# 06_MIMXRT1170_PART2.net
KiCad netlist of a schematic drawn in Altium Designer
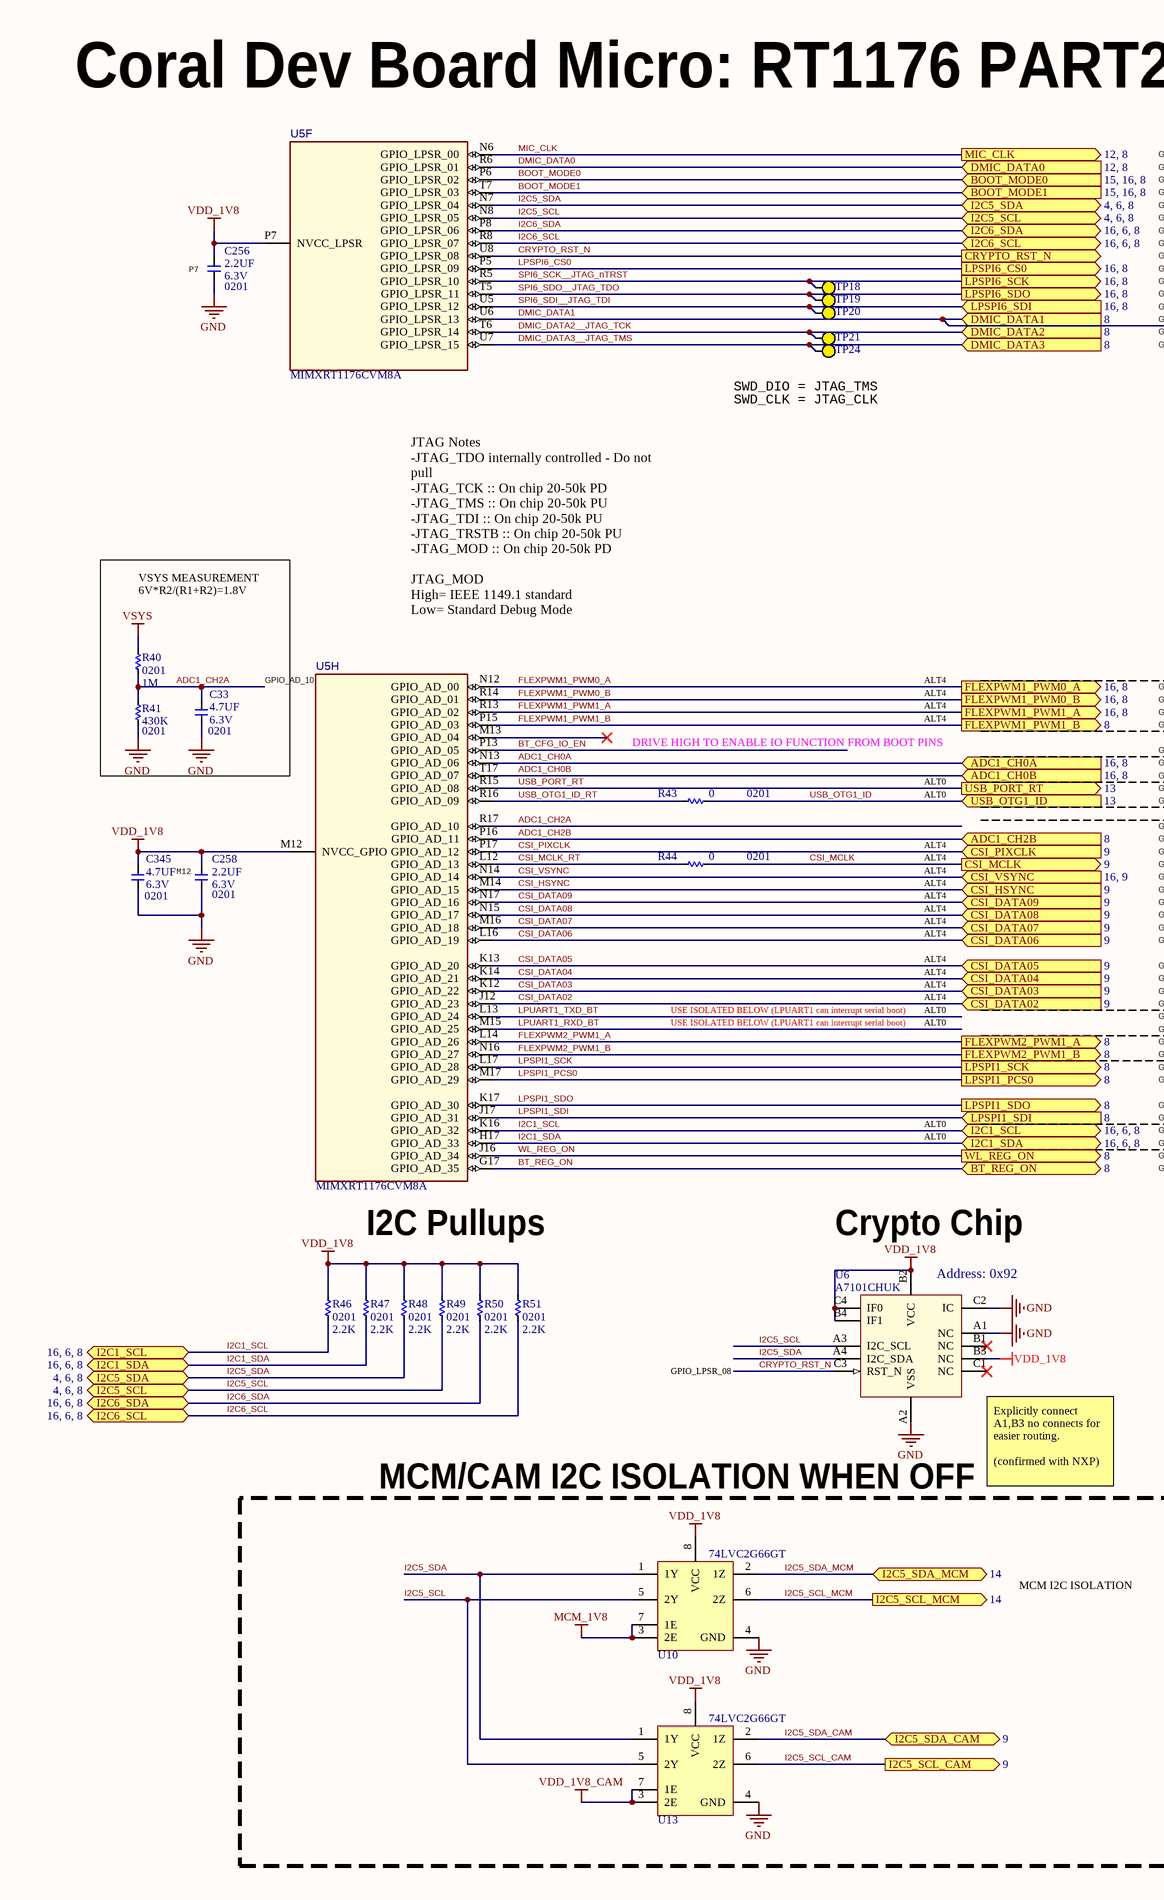
[diagram p0: 06 MIMXRT1170 PART2.SchDoc, left]
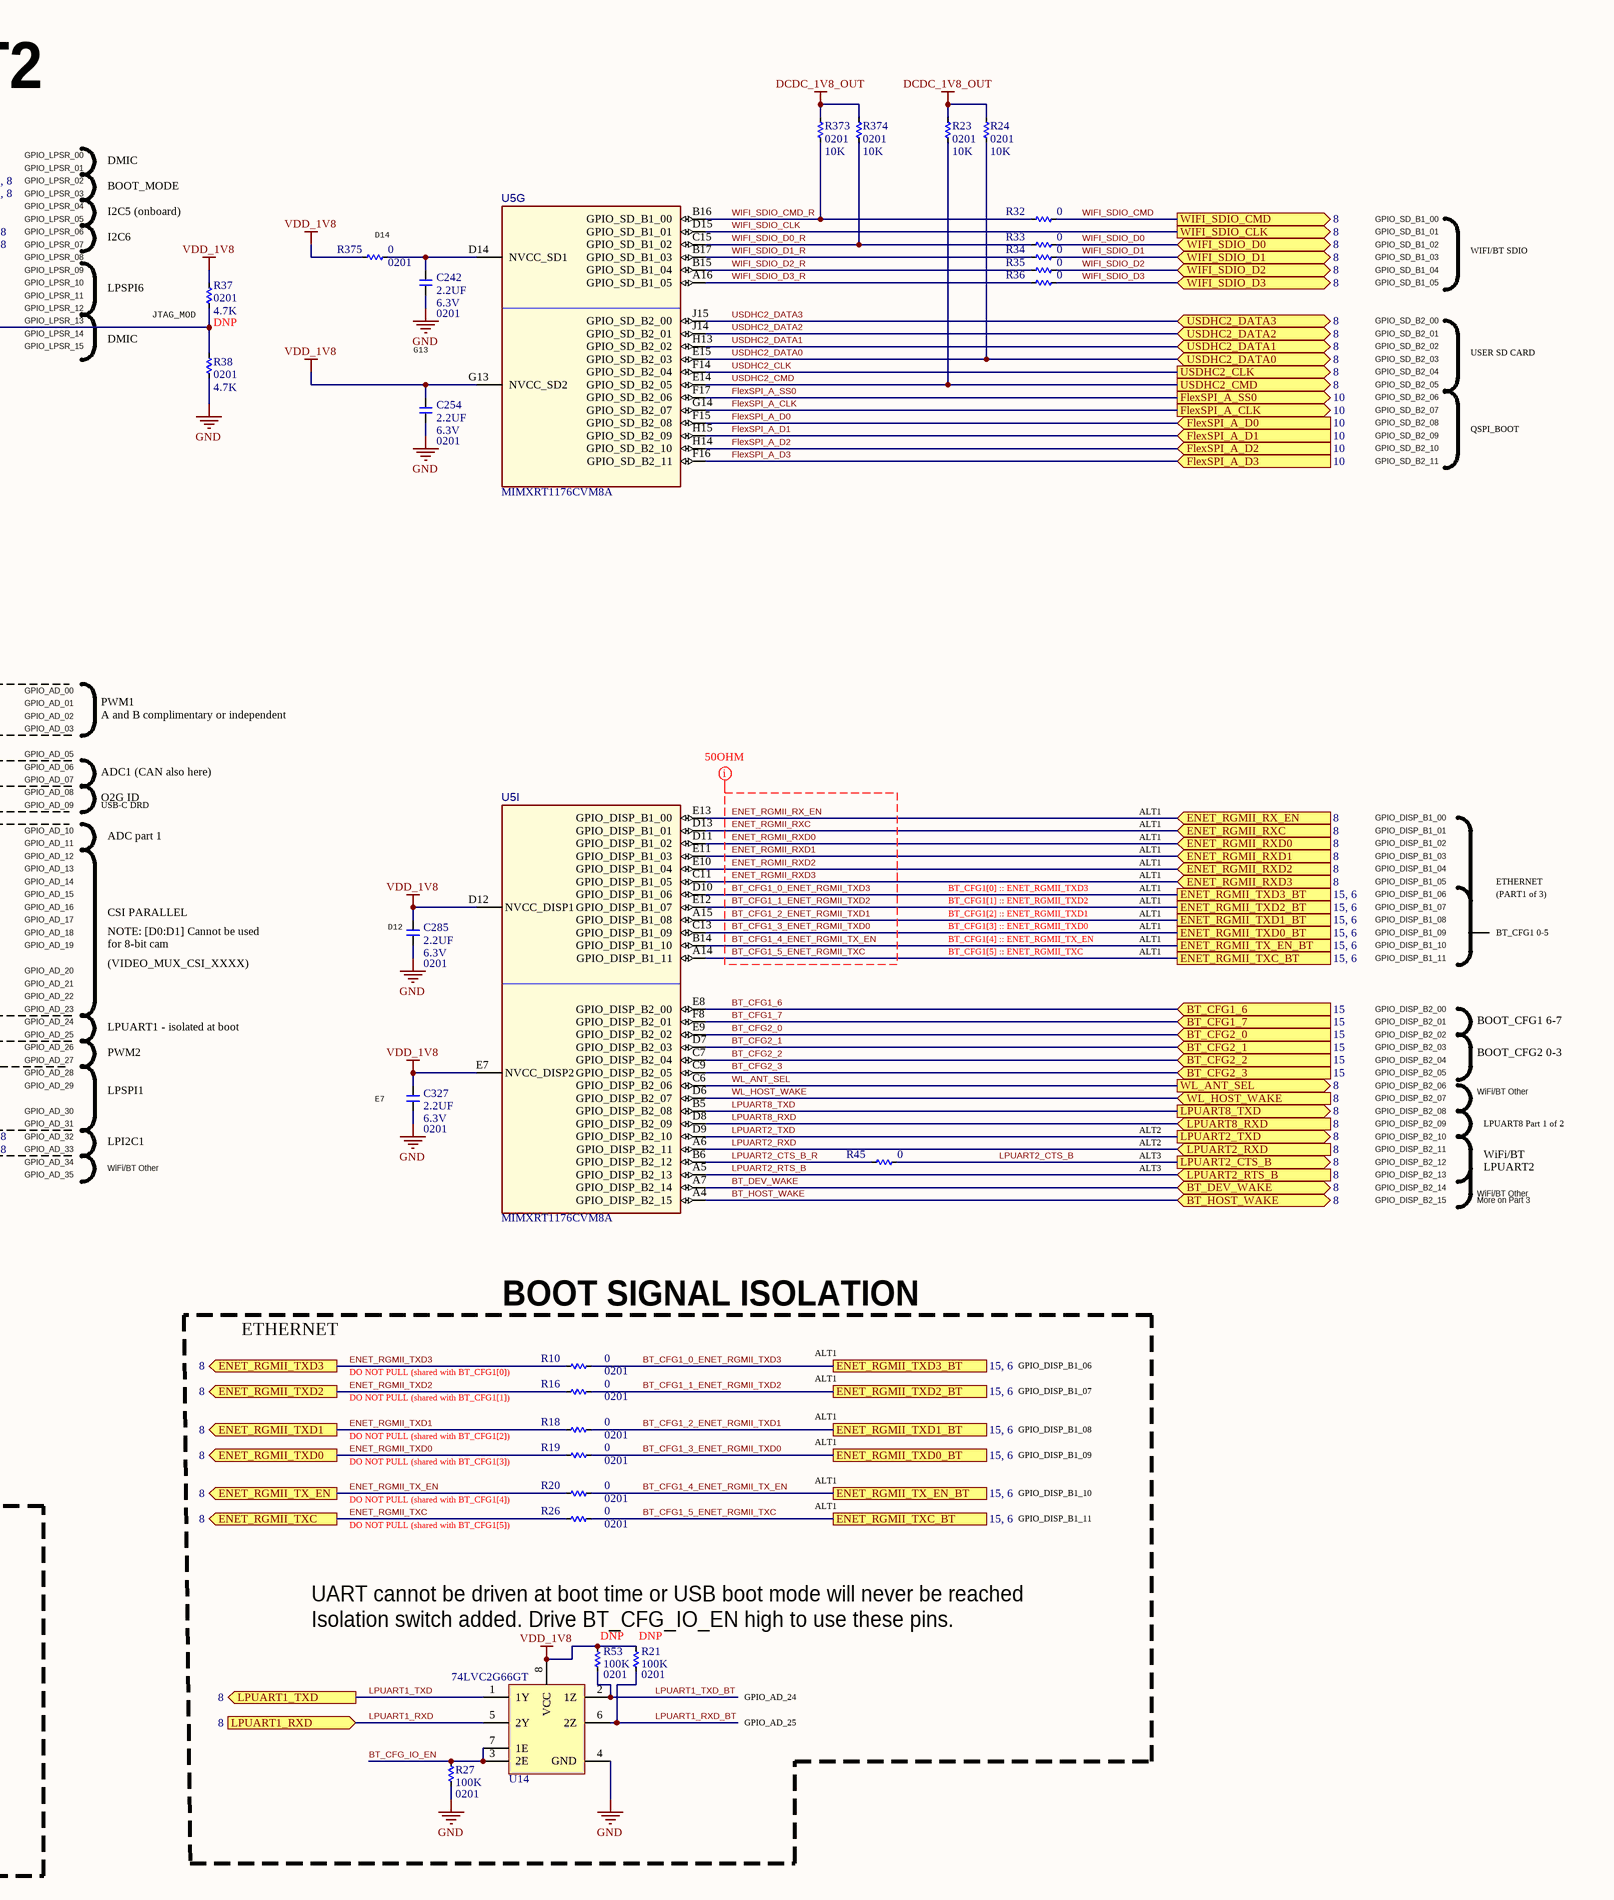
[diagram p1: 06 MIMXRT1170 PART2.SchDoc, right]

(export (version "E")
  (design (tool "Eeschema 10.0.6"))
  (components
    (comp (ref "C33")
      (value "4.7UF")
      (footprint "C0201Y")
      (description "CAP, CER, X5R, 4.7uF, 20%, 6.3V, 0201")
      (fields
        (field (name "MFG") "MURATA")
        (field (name "PACKAGE") "0201")
        (field (name "VOLTAGE") "6.3V")
        (field (name "TOLERANCE") "20%")
      )
      (libsource (lib "AltiumReleaseLibDB") (part "__Template_Cap"))
    )
    (comp (ref "C242")
      (value "2.2UF")
      (footprint "C0201_H0.39MM")
      (description "CAP, CER, X5R, 2.2uF, 20%, 6.3V, 0201, 0.39mm")
      (fields
        (field (name "MFG") "YAGEO")
        (field (name "PACKAGE") "0201")
        (field (name "VOLTAGE") "6.3V")
        (field (name "TOLERANCE") "20%")
      )
      (libsource (lib "AltiumReleaseLibDB") (part "__Template_Cap"))
    )
    (comp (ref "C254")
      (value "2.2UF")
      (footprint "C0201_H0.39MM")
      (description "CAP, CER, X5R, 2.2uF, 20%, 6.3V, 0201, 0.39mm")
      (fields
        (field (name "MFG") "YAGEO")
        (field (name "PACKAGE") "0201")
        (field (name "VOLTAGE") "6.3V")
        (field (name "TOLERANCE") "20%")
      )
      (libsource (lib "AltiumReleaseLibDB") (part "__Template_Cap"))
    )
    (comp (ref "C256")
      (value "2.2UF")
      (footprint "C0201_H0.39MM")
      (description "CAP, CER, X5R, 2.2uF, 20%, 6.3V, 0201, 0.39mm")
      (fields
        (field (name "MFG") "YAGEO")
        (field (name "PACKAGE") "0201")
        (field (name "VOLTAGE") "6.3V")
        (field (name "TOLERANCE") "20%")
      )
      (libsource (lib "AltiumReleaseLibDB") (part "__Template_Cap"))
    )
    (comp (ref "C258")
      (value "2.2UF")
      (footprint "C0201_H0.39MM")
      (description "CAP, CER, X5R, 2.2uF, 20%, 6.3V, 0201, 0.39mm")
      (fields
        (field (name "MFG") "YAGEO")
        (field (name "PACKAGE") "0201")
        (field (name "VOLTAGE") "6.3V")
        (field (name "TOLERANCE") "20%")
      )
      (libsource (lib "AltiumReleaseLibDB") (part "__Template_Cap"))
    )
    (comp (ref "C285")
      (value "2.2UF")
      (footprint "C0201_H0.39MM")
      (description "CAP, CER, X5R, 2.2uF, 20%, 6.3V, 0201, 0.39mm")
      (fields
        (field (name "MFG") "YAGEO")
        (field (name "PACKAGE") "0201")
        (field (name "VOLTAGE") "6.3V")
        (field (name "TOLERANCE") "20%")
      )
      (libsource (lib "AltiumReleaseLibDB") (part "__Template_Cap"))
    )
    (comp (ref "C327")
      (value "2.2UF")
      (footprint "C0201_H0.39MM")
      (description "CAP, CER, X5R, 2.2uF, 20%, 6.3V, 0201, 0.39mm")
      (fields
        (field (name "MFG") "YAGEO")
        (field (name "PACKAGE") "0201")
        (field (name "VOLTAGE") "6.3V")
        (field (name "TOLERANCE") "20%")
      )
      (libsource (lib "AltiumReleaseLibDB") (part "__Template_Cap"))
    )
    (comp (ref "C345")
      (value "4.7UF")
      (footprint "C0201Y")
      (description "CAP, CER, X5R, 4.7uF, 20%, 6.3V, 0201")
      (fields
        (field (name "MFG") "MURATA")
        (field (name "PACKAGE") "0201")
        (field (name "VOLTAGE") "6.3V")
        (field (name "TOLERANCE") "20%")
      )
      (libsource (lib "AltiumReleaseLibDB") (part "__Template_Cap"))
    )
    (comp (ref "R10")
      (value "0")
      (footprint "R0201")
      (description "RES, 0.0, 1/20W, 0201")
      (fields (field (name "MFG") "PANASONIC") (field (name "PACKAGE") "0201") (field (name "POWER") "1/20W"))
      (libsource (lib "AltiumReleaseLibDB") (part "__Template_Resistor"))
    )
    (comp (ref "R16")
      (value "0")
      (footprint "R0201")
      (description "RES, 0.0, 1/20W, 0201")
      (fields (field (name "MFG") "PANASONIC") (field (name "PACKAGE") "0201") (field (name "POWER") "1/20W"))
      (libsource (lib "AltiumReleaseLibDB") (part "__Template_Resistor"))
    )
    (comp (ref "R18")
      (value "0")
      (footprint "R0201")
      (description "RES, 0.0, 1/20W, 0201")
      (fields (field (name "MFG") "PANASONIC") (field (name "PACKAGE") "0201") (field (name "POWER") "1/20W"))
      (libsource (lib "AltiumReleaseLibDB") (part "__Template_Resistor"))
    )
    (comp (ref "R19")
      (value "0")
      (footprint "R0201")
      (description "RES, 0.0, 1/20W, 0201")
      (fields (field (name "MFG") "PANASONIC") (field (name "PACKAGE") "0201") (field (name "POWER") "1/20W"))
      (libsource (lib "AltiumReleaseLibDB") (part "__Template_Resistor"))
    )
    (comp (ref "R20")
      (value "0")
      (footprint "R0201")
      (description "RES, 0.0, 1/20W, 0201")
      (fields (field (name "MFG") "PANASONIC") (field (name "PACKAGE") "0201") (field (name "POWER") "1/20W"))
      (libsource (lib "AltiumReleaseLibDB") (part "__Template_Resistor"))
    )
    (comp (ref "R21")
      (value "100K")
      (footprint "R0201")
      (description "RES, 100K, 1%, 1/20W, 0201")
      (fields
        (field (name "MFG") "PANASONIC")
        (field (name "PACKAGE") "0201")
        (field (name "POWER") "1/20W")
        (field (name "DNP") "DNP")
      )
      (libsource (lib "AltiumReleaseLibDB") (part "__Template_Resistor"))
    )
    (comp (ref "R23")
      (value "10K")
      (footprint "R0201")
      (description "RES, 10K, 1%, 1/20W, 0201")
      (fields (field (name "MFG") "YAGEO") (field (name "PACKAGE") "0201") (field (name "POWER") "1/20W"))
      (libsource (lib "AltiumReleaseLibDB") (part "__Template_Resistor"))
    )
    (comp (ref "R24")
      (value "10K")
      (footprint "R0201")
      (description "RES, 10K, 1%, 1/20W, 0201")
      (fields (field (name "MFG") "YAGEO") (field (name "PACKAGE") "0201") (field (name "POWER") "1/20W"))
      (libsource (lib "AltiumReleaseLibDB") (part "__Template_Resistor"))
    )
    (comp (ref "R26")
      (value "0")
      (footprint "R0201")
      (description "RES, 0.0, 1/20W, 0201")
      (fields (field (name "MFG") "PANASONIC") (field (name "PACKAGE") "0201") (field (name "POWER") "1/20W"))
      (libsource (lib "AltiumReleaseLibDB") (part "__Template_Resistor"))
    )
    (comp (ref "R27")
      (value "100K")
      (footprint "R0201")
      (description "RES, 100K, 1%, 1/20W, 0201")
      (fields (field (name "MFG") "PANASONIC") (field (name "PACKAGE") "0201") (field (name "POWER") "1/20W"))
      (libsource (lib "AltiumReleaseLibDB") (part "__Template_Resistor"))
    )
    (comp (ref "R32")
      (value "0")
      (footprint "R0201")
      (description "RES, 0.0, 1/20W, 0201")
      (fields (field (name "MFG") "PANASONIC") (field (name "POWER") "1/20W"))
      (libsource (lib "AltiumReleaseLibDB") (part "__Template_Resistor"))
    )
    (comp (ref "R33")
      (value "0")
      (footprint "R0201")
      (description "RES, 0.0, 1/20W, 0201")
      (fields (field (name "MFG") "PANASONIC") (field (name "POWER") "1/20W"))
      (libsource (lib "AltiumReleaseLibDB") (part "__Template_Resistor"))
    )
    (comp (ref "R34")
      (value "0")
      (footprint "R0201")
      (description "RES, 0.0, 1/20W, 0201")
      (fields (field (name "MFG") "PANASONIC") (field (name "POWER") "1/20W"))
      (libsource (lib "AltiumReleaseLibDB") (part "__Template_Resistor"))
    )
    (comp (ref "R35")
      (value "0")
      (footprint "R0201")
      (description "RES, 0.0, 1/20W, 0201")
      (fields (field (name "MFG") "PANASONIC") (field (name "POWER") "1/20W"))
      (libsource (lib "AltiumReleaseLibDB") (part "__Template_Resistor"))
    )
    (comp (ref "R36")
      (value "0")
      (footprint "R0201")
      (description "RES, 0.0, 1/20W, 0201")
      (fields (field (name "MFG") "PANASONIC") (field (name "POWER") "1/20W"))
      (libsource (lib "AltiumReleaseLibDB") (part "__Template_Resistor"))
    )
    (comp (ref "R37")
      (value "4.7K")
      (footprint "R0201")
      (description "RES, 4.7K, 5%, 1/20W, 0201")
      (fields
        (field (name "MFG") "YAGEO")
        (field (name "PACKAGE") "0201")
        (field (name "POWER") "1/20W")
        (field (name "DNP") "DNP")
      )
      (libsource (lib "AltiumReleaseLibDB") (part "__Template_Resistor"))
    )
    (comp (ref "R38")
      (value "4.7K")
      (footprint "R0201")
      (description "RES, 4.7K, 5%, 1/20W, 0201")
      (fields (field (name "MFG") "YAGEO") (field (name "PACKAGE") "0201") (field (name "POWER") "1/20W"))
      (libsource (lib "AltiumReleaseLibDB") (part "__Template_Resistor"))
    )
    (comp (ref "R40")
      (value "1M")
      (footprint "R0201")
      (description "RES, 1M, 1%, 1/20W, 0201")
      (fields (field (name "MFG") "PANASONIC") (field (name "PACKAGE") "0201") (field (name "POWER") "1/20W"))
      (libsource (lib "AltiumReleaseLibDB") (part "__Template_Resistor"))
    )
    (comp (ref "R41")
      (value "430K")
      (footprint "R0201")
      (description "Resistor, 430K Ohms, 0201, 0.05W, ±1%")
      (fields (field (name "MFG") "PANASONIC") (field (name "PACKAGE") "0201") (field (name "POWER") "1/20W"))
      (libsource (lib "AltiumReleaseLibDB") (part "__Template_Resistor"))
    )
    (comp (ref "R43")
      (value "0")
      (footprint "R0201")
      (description "RES, 0.0, 1/20W, 0201")
      (fields (field (name "MFG") "PANASONIC") (field (name "PACKAGE") "0201") (field (name "POWER") "1/20W"))
      (libsource (lib "AltiumReleaseLibDB") (part "__Template_Resistor"))
    )
    (comp (ref "R44")
      (value "0")
      (footprint "R0201")
      (description "RES, 0.0, 1/20W, 0201")
      (fields (field (name "MFG") "PANASONIC") (field (name "PACKAGE") "0201") (field (name "POWER") "1/20W"))
      (libsource (lib "AltiumReleaseLibDB") (part "__Template_Resistor"))
    )
    (comp (ref "R45")
      (value "0")
      (footprint "R0201")
      (description "RES, 0.0, 1/20W, 0201")
      (fields (field (name "MFG") "PANASONIC") (field (name "POWER") "1/20W"))
      (libsource (lib "AltiumReleaseLibDB") (part "__Template_Resistor"))
    )
    (comp (ref "R46")
      (value "2.2K")
      (footprint "R0201")
      (description "RES, 2.2K, 5%, 1/20W, 0201")
      (fields (field (name "MFG") "YAGEO") (field (name "PACKAGE") "0201") (field (name "POWER") "1/20W"))
      (libsource (lib "AltiumReleaseLibDB") (part "__Template_Resistor"))
    )
    (comp (ref "R47")
      (value "2.2K")
      (footprint "R0201")
      (description "RES, 2.2K, 5%, 1/20W, 0201")
      (fields (field (name "MFG") "YAGEO") (field (name "PACKAGE") "0201") (field (name "POWER") "1/20W"))
      (libsource (lib "AltiumReleaseLibDB") (part "__Template_Resistor"))
    )
    (comp (ref "R48")
      (value "2.2K")
      (footprint "R0201")
      (description "RES, 2.2K, 5%, 1/20W, 0201")
      (fields (field (name "MFG") "YAGEO") (field (name "PACKAGE") "0201") (field (name "POWER") "1/20W"))
      (libsource (lib "AltiumReleaseLibDB") (part "__Template_Resistor"))
    )
    (comp (ref "R49")
      (value "2.2K")
      (footprint "R0201")
      (description "RES, 2.2K, 5%, 1/20W, 0201")
      (fields (field (name "MFG") "YAGEO") (field (name "PACKAGE") "0201") (field (name "POWER") "1/20W"))
      (libsource (lib "AltiumReleaseLibDB") (part "__Template_Resistor"))
    )
    (comp (ref "R50")
      (value "2.2K")
      (footprint "R0201")
      (description "RES, 2.2K, 5%, 1/20W, 0201")
      (fields (field (name "MFG") "YAGEO") (field (name "PACKAGE") "0201") (field (name "POWER") "1/20W"))
      (libsource (lib "AltiumReleaseLibDB") (part "__Template_Resistor"))
    )
    (comp (ref "R51")
      (value "2.2K")
      (footprint "R0201")
      (description "RES, 2.2K, 5%, 1/20W, 0201")
      (fields (field (name "MFG") "YAGEO") (field (name "PACKAGE") "0201") (field (name "POWER") "1/20W"))
      (libsource (lib "AltiumReleaseLibDB") (part "__Template_Resistor"))
    )
    (comp (ref "R53")
      (value "100K")
      (footprint "R0201")
      (description "RES, 100K, 1%, 1/20W, 0201")
      (fields
        (field (name "MFG") "PANASONIC")
        (field (name "PACKAGE") "0201")
        (field (name "POWER") "1/20W")
        (field (name "DNP") "DNP")
      )
      (libsource (lib "AltiumReleaseLibDB") (part "__Template_Resistor"))
    )
    (comp (ref "R373")
      (value "10K")
      (footprint "R0201")
      (description "RES, 10K, 1%, 1/20W, 0201")
      (fields (field (name "MFG") "YAGEO") (field (name "PACKAGE") "0201") (field (name "POWER") "1/20W"))
      (libsource (lib "AltiumReleaseLibDB") (part "__Template_Resistor"))
    )
    (comp (ref "R374")
      (value "10K")
      (footprint "R0201")
      (description "RES, 10K, 1%, 1/20W, 0201")
      (fields (field (name "MFG") "YAGEO") (field (name "PACKAGE") "0201") (field (name "POWER") "1/20W"))
      (libsource (lib "AltiumReleaseLibDB") (part "__Template_Resistor"))
    )
    (comp (ref "R375")
      (value "0")
      (footprint "R0201")
      (description "RES, 0.0, 1/20W, 0201")
      (fields (field (name "MFG") "PANASONIC") (field (name "PACKAGE") "0201") (field (name "POWER") "1/20W"))
      (libsource (lib "AltiumReleaseLibDB") (part "__Template_Resistor"))
    )
    (comp (ref "TP18")
      (value "TESTPAD_30MIL")
      (footprint "TESTPAD_SMT_30MIL")
      (description "TESTPAD_SMT_30MIL")
      (fields (field (name "MFG") "_PCB Feature"))
      (libsource (lib "AltiumReleaseLibDB") (part "TESTPAD_30MIL"))
    )
    (comp (ref "TP19")
      (value "TESTPAD_30MIL")
      (footprint "TESTPAD_SMT_30MIL")
      (description "TESTPAD_SMT_30MIL")
      (fields (field (name "MFG") "_PCB Feature"))
      (libsource (lib "AltiumReleaseLibDB") (part "TESTPAD_30MIL"))
    )
    (comp (ref "TP20")
      (value "TESTPAD_30MIL")
      (footprint "TESTPAD_SMT_30MIL")
      (description "TESTPAD_SMT_30MIL")
      (fields (field (name "MFG") "_PCB Feature"))
      (libsource (lib "AltiumReleaseLibDB") (part "TESTPAD_30MIL"))
    )
    (comp (ref "TP21")
      (value "TESTPAD_30MIL")
      (footprint "TESTPAD_SMT_30MIL")
      (description "TESTPAD_SMT_30MIL")
      (fields (field (name "MFG") "_PCB Feature"))
      (libsource (lib "AltiumReleaseLibDB") (part "TESTPAD_30MIL"))
    )
    (comp (ref "TP24")
      (value "TESTPAD_30MIL")
      (footprint "TESTPAD_SMT_30MIL")
      (description "TESTPAD_SMT_30MIL")
      (fields (field (name "MFG") "_PCB Feature"))
      (libsource (lib "AltiumReleaseLibDB") (part "TESTPAD_30MIL"))
    )
    (comp (ref "U5")
      (value "MCU_MIMXRT1176CVM8A")
      (footprint "BGA289C80P17X17_1400X14000X152")
      (description "IC, PROCESSOR, MIMXRT1176CV, ARM CORTEX-M4/M7, 2MB RAM, SDRAM, WLAN, BGA-289")
      (fields (field (name "MFG") "NXP Semiconductors") (field (name "MFG P/N") "MIMXRT1176CVM8A"))
      (libsource (lib "AltiumReleaseLibDB") (part "MCU_MIMXRT1176CVM8A"))
    )
    (comp (ref "U6")
      (value "SECUR_AUTH_A7101CHUK")
      (footprint "BGA12C50+3X4_206X202X65")
      (description "IC, MICRO CONTROLLER, A7101, MX51, SECURITY, TEMP, AUTHENTICATION, I2C, WLCSP-12")
      (fields (field (name "MFG") "NXP USA Inc.") (field (name "MFG P/N") "A7101CHUK"))
      (libsource (lib "AltiumReleaseLibDB") (part "SECUR_AUTH_A7101CHUK"))
    )
    (comp (ref "U10")
      (value "74LVC2G66GT")
      (footprint "SON8_0P5_1L95x1W")
      (description "SPST 2x, 1.65V ~ 5.5V, XSON8, 500MHz at 50Ohm")
      (libsource (lib "Valiant_P0") (part "74LVC2G66GT"))
    )
    (comp (ref "U13")
      (value "74LVC2G66GT")
      (footprint "SON8_0P5_1L95x1W")
      (description "SPST 2x, 1.65V ~ 5.5V, XSON8, 500MHz at 50Ohm")
      (libsource (lib "Valiant_P0") (part "74LVC2G66GT"))
    )
    (comp (ref "U14")
      (value "74LVC2G66GT")
      (footprint "SON8_0P5_1L95x1W")
      (description "SPST 2x, 1.65V ~ 5.5V, XSON8, 500MHz at 50Ohm")
      (libsource (lib "Valiant_P0") (part "74LVC2G66GT"))
    )
  )
  (nets
    (net (code "1") (name "/ADC1_CH0A") (class "Default")
      (node (ref "U5") (pin "N13") (pinfunction "GPIO_AD_06_N13") (pintype "bidirectional"))
    )
    (net (code "2") (name "/ADC1_CH0B") (class "Default")
      (node (ref "U5") (pin "T17") (pinfunction "GPIO_AD_07_T17") (pintype "bidirectional"))
    )
    (net (code "3") (name "/ADC1_CH2A") (class "Default")
      (node (ref "C33") (pin "1") (pintype "passive"))
      (node (ref "R40") (pin "1") (pintype "passive"))
      (node (ref "R41") (pin "2") (pintype "passive"))
      (node (ref "U5") (pin "R17") (pinfunction "GPIO_AD_10_R17") (pintype "bidirectional"))
    )
    (net (code "4") (name "/ADC1_CH2B") (class "Default")
      (node (ref "U5") (pin "P16") (pinfunction "GPIO_AD_11_P16") (pintype "bidirectional"))
    )
    (net (code "5") (name "/BOOT_MODE0") (class "Default")
      (node (ref "U5") (pin "P6") (pinfunction "GPIO_LPSR_02_P6") (pintype "bidirectional"))
    )
    (net (code "6") (name "/BOOT_MODE1") (class "Default")
      (node (ref "U5") (pin "T7") (pinfunction "GPIO_LPSR_03_T7") (pintype "bidirectional"))
    )
    (net (code "7") (name "/BT_CFG1_0_ENET_RGMII_TXD3") (class "Default")
      (node (ref "R10") (pin "2") (pintype "passive"))
      (node (ref "U5") (pin "D10") (pinfunction "GPIO_DISP_B1_06_D10") (pintype "bidirectional"))
    )
    (net (code "8") (name "/BT_CFG1_1_ENET_RGMII_TXD2") (class "Default")
      (node (ref "R16") (pin "2") (pintype "passive"))
      (node (ref "U5") (pin "E12") (pinfunction "GPIO_DISP_B1_07_E12") (pintype "bidirectional"))
    )
    (net (code "9") (name "/BT_CFG1_2_ENET_RGMII_TXD1") (class "Default")
      (node (ref "R18") (pin "2") (pintype "passive"))
      (node (ref "U5") (pin "A15") (pinfunction "GPIO_DISP_B1_08_A15") (pintype "bidirectional"))
    )
    (net (code "10") (name "/BT_CFG1_3_ENET_RGMII_TXD0") (class "Default")
      (node (ref "R19") (pin "2") (pintype "passive"))
      (node (ref "U5") (pin "C13") (pinfunction "GPIO_DISP_B1_09_C13") (pintype "bidirectional"))
    )
    (net (code "11") (name "/BT_CFG1_4_ENET_RGMII_TX_EN") (class "Default")
      (node (ref "R20") (pin "2") (pintype "passive"))
      (node (ref "U5") (pin "B14") (pinfunction "GPIO_DISP_B1_10_B14") (pintype "bidirectional"))
    )
    (net (code "12") (name "/BT_CFG1_5_ENET_RGMII_TXC") (class "Default")
      (node (ref "R26") (pin "2") (pintype "passive"))
      (node (ref "U5") (pin "A14") (pinfunction "GPIO_DISP_B1_11_A14") (pintype "bidirectional"))
    )
    (net (code "13") (name "/BT_CFG1_6") (class "Default")
      (node (ref "U5") (pin "E8") (pinfunction "GPIO_DISP_B2_00_E8") (pintype "bidirectional"))
    )
    (net (code "14") (name "/BT_CFG1_7") (class "Default")
      (node (ref "U5") (pin "F8") (pinfunction "GPIO_DISP_B2_01_F8") (pintype "bidirectional"))
    )
    (net (code "15") (name "/BT_CFG2_0") (class "Default")
      (node (ref "U5") (pin "E9") (pinfunction "GPIO_DISP_B2_02_E9") (pintype "bidirectional"))
    )
    (net (code "16") (name "/BT_CFG2_1") (class "Default")
      (node (ref "U5") (pin "D7") (pinfunction "GPIO_DISP_B2_03_D7") (pintype "bidirectional"))
    )
    (net (code "17") (name "/BT_CFG2_2") (class "Default")
      (node (ref "U5") (pin "C7") (pinfunction "GPIO_DISP_B2_04_C7") (pintype "bidirectional"))
    )
    (net (code "18") (name "/BT_CFG2_3") (class "Default")
      (node (ref "U5") (pin "C9") (pinfunction "GPIO_DISP_B2_05_C9") (pintype "bidirectional"))
    )
    (net (code "19") (name "/BT_CFG_IO_EN") (class "Default")
      (node (ref "R27") (pin "2") (pintype "passive"))
      (node (ref "U14") (pin "3") (pinfunction "2E_3") (pintype "passive"))
      (node (ref "U14") (pin "7") (pinfunction "1E_7") (pintype "passive"))
      (node (ref "U5") (pin "P13") (pinfunction "GPIO_AD_05_P13") (pintype "bidirectional"))
    )
    (net (code "20") (name "/BT_DEV_WAKE") (class "Default")
      (node (ref "U5") (pin "A7") (pinfunction "GPIO_DISP_B2_14_A7") (pintype "bidirectional"))
    )
    (net (code "21") (name "/BT_HOST_WAKE") (class "Default")
      (node (ref "U5") (pin "A4") (pinfunction "GPIO_DISP_B2_15_A4") (pintype "bidirectional"))
    )
    (net (code "22") (name "/BT_REG_ON") (class "Default")
      (node (ref "U5") (pin "G17") (pinfunction "GPIO_AD_35_G17") (pintype "bidirectional"))
    )
    (net (code "23") (name "/CRYPTO_RST_N") (class "Default")
      (node (ref "U5") (pin "U8") (pinfunction "GPIO_LPSR_08_U8") (pintype "bidirectional"))
      (node (ref "U6") (pin "C3") (pinfunction "RST_N_C3") (pintype "input"))
    )
    (net (code "24") (name "/CSI_DATA02") (class "Default")
      (node (ref "U5") (pin "J12") (pinfunction "GPIO_AD_23_J12") (pintype "bidirectional"))
    )
    (net (code "25") (name "/CSI_DATA03") (class "Default")
      (node (ref "U5") (pin "K12") (pinfunction "GPIO_AD_22_K12") (pintype "bidirectional"))
    )
    (net (code "26") (name "/CSI_DATA04") (class "Default")
      (node (ref "U5") (pin "K14") (pinfunction "GPIO_AD_21_K14") (pintype "bidirectional"))
    )
    (net (code "27") (name "/CSI_DATA05") (class "Default")
      (node (ref "U5") (pin "K13") (pinfunction "GPIO_AD_20_K13") (pintype "bidirectional"))
    )
    (net (code "28") (name "/CSI_DATA06") (class "Default")
      (node (ref "U5") (pin "L16") (pinfunction "GPIO_AD_19_L16") (pintype "bidirectional"))
    )
    (net (code "29") (name "/CSI_DATA07") (class "Default")
      (node (ref "U5") (pin "M16") (pinfunction "GPIO_AD_18_M16") (pintype "bidirectional"))
    )
    (net (code "30") (name "/CSI_DATA08") (class "Default")
      (node (ref "U5") (pin "N15") (pinfunction "GPIO_AD_17_N15") (pintype "bidirectional"))
    )
    (net (code "31") (name "/CSI_DATA09") (class "Default")
      (node (ref "U5") (pin "N17") (pinfunction "GPIO_AD_16_N17") (pintype "bidirectional"))
    )
    (net (code "32") (name "/CSI_HSYNC") (class "Default")
      (node (ref "U5") (pin "M14") (pinfunction "GPIO_AD_15_M14") (pintype "bidirectional"))
    )
    (net (code "33") (name "/CSI_MCLK") (class "Default") (node (ref "R44") (pin "2") (pintype "passive")))
    (net (code "34") (name "/CSI_MCLK_RT") (class "Default")
      (node (ref "R44") (pin "1") (pintype "passive"))
      (node (ref "U5") (pin "L12") (pinfunction "GPIO_AD_13_L12") (pintype "bidirectional"))
    )
    (net (code "35") (name "/CSI_PIXCLK") (class "Default")
      (node (ref "U5") (pin "P17") (pinfunction "GPIO_AD_12_P17") (pintype "bidirectional"))
    )
    (net (code "36") (name "/CSI_VSYNC") (class "Default")
      (node (ref "U5") (pin "N14") (pinfunction "GPIO_AD_14_N14") (pintype "bidirectional"))
    )
    (net (code "37") (name "/DMIC_DATA0") (class "Default")
      (node (ref "U5") (pin "R6") (pinfunction "GPIO_LPSR_01_R6") (pintype "bidirectional"))
    )
    (net (code "38") (name "/DMIC_DATA1") (class "Default")
      (node (ref "R37") (pin "1") (pintype "passive"))
      (node (ref "R38") (pin "2") (pintype "passive"))
      (node (ref "U5") (pin "U6") (pinfunction "GPIO_LPSR_13_U6") (pintype "bidirectional"))
    )
    (net (code "39") (name "/DMIC_DATA2__JTAG_TCK") (class "Default")
      (node (ref "TP21") (pin "1") (pintype "passive"))
      (node (ref "U5") (pin "T6") (pinfunction "GPIO_LPSR_14_T6") (pintype "bidirectional"))
    )
    (net (code "40") (name "/DMIC_DATA3__JTAG_TMS") (class "Default")
      (node (ref "TP24") (pin "1") (pintype "passive"))
      (node (ref "U5") (pin "U7") (pinfunction "GPIO_LPSR_15_U7") (pintype "bidirectional"))
    )
    (net (code "41") (name "/ENET_RGMII_RXC") (class "Default")
      (node (ref "U5") (pin "D13") (pinfunction "GPIO_DISP_B1_01_D13") (pintype "bidirectional"))
    )
    (net (code "42") (name "/ENET_RGMII_RXD0") (class "Default")
      (node (ref "U5") (pin "D11") (pinfunction "GPIO_DISP_B1_02_D11") (pintype "bidirectional"))
    )
    (net (code "43") (name "/ENET_RGMII_RXD1") (class "Default")
      (node (ref "U5") (pin "E11") (pinfunction "GPIO_DISP_B1_03_E11") (pintype "bidirectional"))
    )
    (net (code "44") (name "/ENET_RGMII_RXD2") (class "Default")
      (node (ref "U5") (pin "E10") (pinfunction "GPIO_DISP_B1_04_E10") (pintype "bidirectional"))
    )
    (net (code "45") (name "/ENET_RGMII_RXD3") (class "Default")
      (node (ref "U5") (pin "C11") (pinfunction "GPIO_DISP_B1_05_C11") (pintype "bidirectional"))
    )
    (net (code "46") (name "/ENET_RGMII_RX_EN") (class "Default")
      (node (ref "U5") (pin "E13") (pinfunction "GPIO_DISP_B1_00_E13") (pintype "bidirectional"))
    )
    (net (code "47") (name "/ENET_RGMII_TXC") (class "Default")
      (node (ref "R26") (pin "1") (pintype "passive"))
    )
    (net (code "48") (name "/ENET_RGMII_TXD0") (class "Default")
      (node (ref "R19") (pin "1") (pintype "passive"))
    )
    (net (code "49") (name "/ENET_RGMII_TXD1") (class "Default")
      (node (ref "R18") (pin "1") (pintype "passive"))
    )
    (net (code "50") (name "/ENET_RGMII_TXD2") (class "Default")
      (node (ref "R16") (pin "1") (pintype "passive"))
    )
    (net (code "51") (name "/ENET_RGMII_TXD3") (class "Default")
      (node (ref "R10") (pin "1") (pintype "passive"))
    )
    (net (code "52") (name "/ENET_RGMII_TX_EN") (class "Default")
      (node (ref "R20") (pin "1") (pintype "passive"))
    )
    (net (code "53") (name "/FLEXPWM1_PWM0_A") (class "Default")
      (node (ref "U5") (pin "N12") (pinfunction "GPIO_AD_00_N12") (pintype "bidirectional"))
    )
    (net (code "54") (name "/FLEXPWM1_PWM0_B") (class "Default")
      (node (ref "U5") (pin "R14") (pinfunction "GPIO_AD_01_R14") (pintype "bidirectional"))
    )
    (net (code "55") (name "/FLEXPWM1_PWM1_A") (class "Default")
      (node (ref "U5") (pin "R13") (pinfunction "GPIO_AD_02_R13") (pintype "bidirectional"))
    )
    (net (code "56") (name "/FLEXPWM1_PWM1_B") (class "Default")
      (node (ref "U5") (pin "P15") (pinfunction "GPIO_AD_03_P15") (pintype "bidirectional"))
    )
    (net (code "57") (name "/FLEXPWM2_PWM1_A") (class "Default")
      (node (ref "U5") (pin "L14") (pinfunction "GPIO_AD_26_L14") (pintype "bidirectional"))
    )
    (net (code "58") (name "/FLEXPWM2_PWM1_B") (class "Default")
      (node (ref "U5") (pin "N16") (pinfunction "GPIO_AD_27_N16") (pintype "bidirectional"))
    )
    (net (code "59") (name "/FlexSPI_A_CLK") (class "Default")
      (node (ref "U5") (pin "G14") (pinfunction "GPIO_SD_B2_07_G14") (pintype "bidirectional"))
    )
    (net (code "60") (name "/FlexSPI_A_D0") (class "Default")
      (node (ref "U5") (pin "F15") (pinfunction "GPIO_SD_B2_08_F15") (pintype "bidirectional"))
    )
    (net (code "61") (name "/FlexSPI_A_D1") (class "Default")
      (node (ref "U5") (pin "H15") (pinfunction "GPIO_SD_B2_09_H15") (pintype "bidirectional"))
    )
    (net (code "62") (name "/FlexSPI_A_D2") (class "Default")
      (node (ref "U5") (pin "H14") (pinfunction "GPIO_SD_B2_10_H14") (pintype "bidirectional"))
    )
    (net (code "63") (name "/FlexSPI_A_D3") (class "Default")
      (node (ref "U5") (pin "F16") (pinfunction "GPIO_SD_B2_11_F16") (pintype "bidirectional"))
    )
    (net (code "64") (name "/FlexSPI_A_SS0") (class "Default")
      (node (ref "U5") (pin "F17") (pinfunction "GPIO_SD_B2_06_F17") (pintype "bidirectional"))
    )
    (net (code "65") (name "/I2C1_SCL") (class "Default")
      (node (ref "R46") (pin "1") (pintype "passive"))
      (node (ref "U5") (pin "K16") (pinfunction "GPIO_AD_32_K16") (pintype "bidirectional"))
    )
    (net (code "66") (name "/I2C1_SDA") (class "Default")
      (node (ref "R47") (pin "1") (pintype "passive"))
      (node (ref "U5") (pin "H17") (pinfunction "GPIO_AD_33_H17") (pintype "bidirectional"))
    )
    (net (code "67") (name "/I2C5_SCL") (class "Default")
      (node (ref "R49") (pin "1") (pintype "passive"))
      (node (ref "U10") (pin "5") (pinfunction "2Y_5") (pintype "passive"))
      (node (ref "U13") (pin "5") (pinfunction "2Y_5") (pintype "passive"))
      (node (ref "U5") (pin "N8") (pinfunction "GPIO_LPSR_05_N8") (pintype "bidirectional"))
      (node (ref "U6") (pin "A3") (pinfunction "I2C_SCL_A3") (pintype "passive"))
    )
    (net (code "68") (name "/I2C5_SCL_CAM") (class "Default")
      (node (ref "U13") (pin "6") (pinfunction "2Z_6") (pintype "passive"))
    )
    (net (code "69") (name "/I2C5_SCL_MCM") (class "Default")
      (node (ref "U10") (pin "6") (pinfunction "2Z_6") (pintype "passive"))
    )
    (net (code "70") (name "/I2C5_SDA") (class "Default")
      (node (ref "R48") (pin "1") (pintype "passive"))
      (node (ref "U10") (pin "1") (pinfunction "1Y_1") (pintype "passive"))
      (node (ref "U13") (pin "1") (pinfunction "1Y_1") (pintype "passive"))
      (node (ref "U5") (pin "N7") (pinfunction "GPIO_LPSR_04_N7") (pintype "bidirectional"))
      (node (ref "U6") (pin "A4") (pinfunction "I2C_SDA_A4") (pintype "passive"))
    )
    (net (code "71") (name "/I2C5_SDA_CAM") (class "Default")
      (node (ref "U13") (pin "2") (pinfunction "1Z_2") (pintype "passive"))
    )
    (net (code "72") (name "/I2C5_SDA_MCM") (class "Default")
      (node (ref "U10") (pin "2") (pinfunction "1Z_2") (pintype "passive"))
    )
    (net (code "73") (name "/I2C6_SCL") (class "Default")
      (node (ref "R51") (pin "1") (pintype "passive"))
      (node (ref "U5") (pin "R8") (pinfunction "GPIO_LPSR_07_R8") (pintype "bidirectional"))
    )
    (net (code "74") (name "/I2C6_SDA") (class "Default")
      (node (ref "R50") (pin "1") (pintype "passive"))
      (node (ref "U5") (pin "P8") (pinfunction "GPIO_LPSR_06_P8") (pintype "bidirectional"))
    )
    (net (code "75") (name "/LPSPI1_PCS0") (class "Default")
      (node (ref "U5") (pin "M17") (pinfunction "GPIO_AD_29_M17") (pintype "bidirectional"))
    )
    (net (code "76") (name "/LPSPI1_SCK") (class "Default")
      (node (ref "U5") (pin "L17") (pinfunction "GPIO_AD_28_L17") (pintype "bidirectional"))
    )
    (net (code "77") (name "/LPSPI1_SDI") (class "Default")
      (node (ref "U5") (pin "J17") (pinfunction "GPIO_AD_31_J17") (pintype "bidirectional"))
    )
    (net (code "78") (name "/LPSPI1_SDO") (class "Default")
      (node (ref "U5") (pin "K17") (pinfunction "GPIO_AD_30_K17") (pintype "bidirectional"))
    )
    (net (code "79") (name "/LPSPI6_CS0") (class "Default")
      (node (ref "U5") (pin "P5") (pinfunction "GPIO_LPSR_09_P5") (pintype "bidirectional"))
    )
    (net (code "80") (name "/LPUART1_RXD") (class "Default")
      (node (ref "U14") (pin "5") (pinfunction "2Y_5") (pintype "passive"))
    )
    (net (code "81") (name "/LPUART1_RXD_BT") (class "Default")
      (node (ref "R21") (pin "1") (pintype "passive"))
      (node (ref "U14") (pin "6") (pinfunction "2Z_6") (pintype "passive"))
      (node (ref "U5") (pin "M15") (pinfunction "GPIO_AD_25_M15") (pintype "bidirectional"))
    )
    (net (code "82") (name "/LPUART1_TXD") (class "Default")
      (node (ref "U14") (pin "1") (pinfunction "1Y_1") (pintype "passive"))
    )
    (net (code "83") (name "/LPUART1_TXD_BT") (class "Default")
      (node (ref "R53") (pin "1") (pintype "passive"))
      (node (ref "U14") (pin "2") (pinfunction "1Z_2") (pintype "passive"))
      (node (ref "U5") (pin "L13") (pinfunction "GPIO_AD_24_L13") (pintype "bidirectional"))
    )
    (net (code "84") (name "/LPUART2_CTS_B") (class "Default")
      (node (ref "R45") (pin "2") (pintype "passive"))
    )
    (net (code "85") (name "/LPUART2_CTS_B_R") (class "Default")
      (node (ref "R45") (pin "1") (pintype "passive"))
      (node (ref "U5") (pin "B6") (pinfunction "GPIO_DISP_B2_12_B6") (pintype "bidirectional"))
    )
    (net (code "86") (name "/LPUART2_RTS_B") (class "Default")
      (node (ref "U5") (pin "A5") (pinfunction "GPIO_DISP_B2_13_A5") (pintype "bidirectional"))
    )
    (net (code "87") (name "/LPUART2_RXD") (class "Default")
      (node (ref "U5") (pin "A6") (pinfunction "GPIO_DISP_B2_11_A6") (pintype "bidirectional"))
    )
    (net (code "88") (name "/LPUART2_TXD") (class "Default")
      (node (ref "U5") (pin "D9") (pinfunction "GPIO_DISP_B2_10_D9") (pintype "bidirectional"))
    )
    (net (code "89") (name "/LPUART8_RXD") (class "Default")
      (node (ref "U5") (pin "D8") (pinfunction "GPIO_DISP_B2_09_D8") (pintype "bidirectional"))
    )
    (net (code "90") (name "/LPUART8_TXD") (class "Default")
      (node (ref "U5") (pin "B5") (pinfunction "GPIO_DISP_B2_08_B5") (pintype "bidirectional"))
    )
    (net (code "91") (name "/MIC_CLK") (class "Default")
      (node (ref "U5") (pin "N6") (pinfunction "GPIO_LPSR_00_N6") (pintype "bidirectional"))
    )
    (net (code "92") (name "/SPI6_SCK__JTAG_nTRST") (class "Default")
      (node (ref "TP18") (pin "1") (pintype "passive"))
      (node (ref "U5") (pin "R5") (pinfunction "GPIO_LPSR_10_R5") (pintype "bidirectional"))
    )
    (net (code "93") (name "/SPI6_SDI__JTAG_TDI") (class "Default")
      (node (ref "TP20") (pin "1") (pintype "passive"))
      (node (ref "U5") (pin "U5") (pinfunction "GPIO_LPSR_12_U5") (pintype "bidirectional"))
    )
    (net (code "94") (name "/SPI6_SDO__JTAG_TDO") (class "Default")
      (node (ref "TP19") (pin "1") (pintype "passive"))
      (node (ref "U5") (pin "T5") (pinfunction "GPIO_LPSR_11_T5") (pintype "bidirectional"))
    )
    (net (code "95") (name "/USB_OTG1_ID") (class "Default") (node (ref "R43") (pin "2") (pintype "passive")))
    (net (code "96") (name "/USB_OTG1_ID_RT") (class "Default")
      (node (ref "R43") (pin "1") (pintype "passive"))
      (node (ref "U5") (pin "R16") (pinfunction "GPIO_AD_09_R16") (pintype "bidirectional"))
    )
    (net (code "97") (name "/USB_PORT_RT") (class "Default")
      (node (ref "U5") (pin "R15") (pinfunction "GPIO_AD_08_R15") (pintype "bidirectional"))
    )
    (net (code "98") (name "/USDHC2_CLK") (class "Default")
      (node (ref "U5") (pin "F14") (pinfunction "GPIO_SD_B2_04_F14") (pintype "bidirectional"))
    )
    (net (code "99") (name "/USDHC2_CMD") (class "Default")
      (node (ref "R23") (pin "1") (pintype "passive"))
      (node (ref "U5") (pin "E14") (pinfunction "GPIO_SD_B2_05_E14") (pintype "bidirectional"))
    )
    (net (code "100") (name "/USDHC2_DATA0") (class "Default")
      (node (ref "R24") (pin "1") (pintype "passive"))
      (node (ref "U5") (pin "E15") (pinfunction "GPIO_SD_B2_03_E15") (pintype "bidirectional"))
    )
    (net (code "101") (name "/USDHC2_DATA1") (class "Default")
      (node (ref "U5") (pin "H13") (pinfunction "GPIO_SD_B2_02_H13") (pintype "bidirectional"))
    )
    (net (code "102") (name "/USDHC2_DATA2") (class "Default")
      (node (ref "U5") (pin "J14") (pinfunction "GPIO_SD_B2_01_J14") (pintype "bidirectional"))
    )
    (net (code "103") (name "/USDHC2_DATA3") (class "Default")
      (node (ref "U5") (pin "J15") (pinfunction "GPIO_SD_B2_00_J15") (pintype "bidirectional"))
    )
    (net (code "104") (name "/WIFI_SDIO_CLK") (class "Default")
      (node (ref "U5") (pin "D15") (pinfunction "GPIO_SD_B1_01_D15") (pintype "bidirectional"))
    )
    (net (code "105") (name "/WIFI_SDIO_CMD") (class "Default")
      (node (ref "R32") (pin "2") (pintype "passive"))
    )
    (net (code "106") (name "/WIFI_SDIO_CMD_R") (class "Default")
      (node (ref "R32") (pin "1") (pintype "passive"))
      (node (ref "R373") (pin "1") (pintype "passive"))
      (node (ref "U5") (pin "B16") (pinfunction "GPIO_SD_B1_00_B16") (pintype "bidirectional"))
    )
    (net (code "107") (name "/WIFI_SDIO_D0") (class "Default")
      (node (ref "R33") (pin "2") (pintype "passive"))
    )
    (net (code "108") (name "/WIFI_SDIO_D0_R") (class "Default")
      (node (ref "R33") (pin "1") (pintype "passive"))
      (node (ref "R374") (pin "1") (pintype "passive"))
      (node (ref "U5") (pin "C15") (pinfunction "GPIO_SD_B1_02_C15") (pintype "bidirectional"))
    )
    (net (code "109") (name "/WIFI_SDIO_D1") (class "Default")
      (node (ref "R34") (pin "2") (pintype "passive"))
    )
    (net (code "110") (name "/WIFI_SDIO_D1_R") (class "Default")
      (node (ref "R34") (pin "1") (pintype "passive"))
      (node (ref "U5") (pin "B17") (pinfunction "GPIO_SD_B1_03_B17") (pintype "bidirectional"))
    )
    (net (code "111") (name "/WIFI_SDIO_D2") (class "Default")
      (node (ref "R35") (pin "2") (pintype "passive"))
    )
    (net (code "112") (name "/WIFI_SDIO_D2_R") (class "Default")
      (node (ref "R35") (pin "1") (pintype "passive"))
      (node (ref "U5") (pin "B15") (pinfunction "GPIO_SD_B1_04_B15") (pintype "bidirectional"))
    )
    (net (code "113") (name "/WIFI_SDIO_D3") (class "Default")
      (node (ref "R36") (pin "2") (pintype "passive"))
    )
    (net (code "114") (name "/WIFI_SDIO_D3_R") (class "Default")
      (node (ref "R36") (pin "1") (pintype "passive"))
      (node (ref "U5") (pin "A16") (pinfunction "GPIO_SD_B1_05_A16") (pintype "bidirectional"))
    )
    (net (code "115") (name "/WL_ANT_SEL") (class "Default")
      (node (ref "U5") (pin "C6") (pinfunction "GPIO_DISP_B2_06_C6") (pintype "bidirectional"))
    )
    (net (code "116") (name "/WL_HOST_WAKE") (class "Default")
      (node (ref "U5") (pin "D6") (pinfunction "GPIO_DISP_B2_07_D6") (pintype "bidirectional"))
    )
    (net (code "117") (name "/WL_REG_ON") (class "Default")
      (node (ref "U5") (pin "J16") (pinfunction "GPIO_AD_34_J16") (pintype "bidirectional"))
    )
    (net (code "118") (name "DCDC_1V8_OUT") (class "Default")
      (node (ref "R23") (pin "2") (pintype "passive"))
      (node (ref "R24") (pin "2") (pintype "passive"))
      (node (ref "R373") (pin "2") (pintype "passive"))
      (node (ref "R374") (pin "2") (pintype "passive"))
    )
    (net (code "119") (name "GND") (class "Default")
      (node (ref "C242") (pin "2") (pintype "passive"))
      (node (ref "C254") (pin "2") (pintype "passive"))
      (node (ref "C256") (pin "2") (pintype "passive"))
      (node (ref "C258") (pin "2") (pintype "passive"))
      (node (ref "C285") (pin "2") (pintype "passive"))
      (node (ref "C327") (pin "2") (pintype "passive"))
      (node (ref "C33") (pin "2") (pintype "passive"))
      (node (ref "C345") (pin "2") (pintype "passive"))
      (node (ref "R27") (pin "1") (pintype "passive"))
      (node (ref "R38") (pin "1") (pintype "passive"))
      (node (ref "R41") (pin "1") (pintype "passive"))
      (node (ref "U10") (pin "4") (pinfunction "GND_4") (pintype "passive"))
      (node (ref "U13") (pin "4") (pinfunction "GND_4") (pintype "passive"))
      (node (ref "U14") (pin "4") (pinfunction "GND_4") (pintype "passive"))
      (node (ref "U6") (pin "A1") (pinfunction "NC_A1") (pintype "passive"))
      (node (ref "U6") (pin "A2") (pinfunction "VSS_A2") (pintype "power_in"))
      (node (ref "U6") (pin "C2") (pinfunction "IC_C2") (pintype "passive"))
    )
    (net (code "120") (name "MCM_1V8") (class "Default")
      (node (ref "U10") (pin "3") (pinfunction "2E_3") (pintype "passive"))
      (node (ref "U10") (pin "7") (pinfunction "1E_7") (pintype "passive"))
    )
    (net (code "121") (name "Net-(U5G-NVCC_SD1)") (class "Default")
      (node (ref "C242") (pin "1") (pintype "passive"))
      (node (ref "R375") (pin "2") (pintype "passive"))
      (node (ref "U5") (pin "D14") (pinfunction "NVCC_SD1_D14") (pintype "power_in"))
    )
    (net (code "122") (name "VDD_1V8") (class "Default")
      (node (ref "C254") (pin "1") (pintype "passive"))
      (node (ref "C256") (pin "1") (pintype "passive"))
      (node (ref "C258") (pin "1") (pintype "passive"))
      (node (ref "C285") (pin "1") (pintype "passive"))
      (node (ref "C327") (pin "1") (pintype "passive"))
      (node (ref "C345") (pin "1") (pintype "passive"))
      (node (ref "R21") (pin "2") (pintype "passive"))
      (node (ref "R37") (pin "2") (pintype "passive"))
      (node (ref "R375") (pin "1") (pintype "passive"))
      (node (ref "R46") (pin "2") (pintype "passive"))
      (node (ref "R47") (pin "2") (pintype "passive"))
      (node (ref "R48") (pin "2") (pintype "passive"))
      (node (ref "R49") (pin "2") (pintype "passive"))
      (node (ref "R50") (pin "2") (pintype "passive"))
      (node (ref "R51") (pin "2") (pintype "passive"))
      (node (ref "R53") (pin "2") (pintype "passive"))
      (node (ref "U10") (pin "8") (pinfunction "VCC_8") (pintype "passive"))
      (node (ref "U13") (pin "8") (pinfunction "VCC_8") (pintype "passive"))
      (node (ref "U14") (pin "8") (pinfunction "VCC_8") (pintype "passive"))
      (node (ref "U5") (pin "D12") (pinfunction "NVCC_DISP1_D12") (pintype "passive"))
      (node (ref "U5") (pin "E7") (pinfunction "NVCC_DISP2_E7") (pintype "passive"))
      (node (ref "U5") (pin "G13") (pinfunction "NVCC_SD2_G13") (pintype "power_in"))
      (node (ref "U5") (pin "M12") (pinfunction "NVCC_GPIO_M12") (pintype "power_in"))
      (node (ref "U5") (pin "P7") (pinfunction "NVCC_LPSR_P7") (pintype "passive"))
      (node (ref "U6") (pin "B2") (pinfunction "VCC_B2") (pintype "power_in"))
      (node (ref "U6") (pin "B3") (pinfunction "NC_B3") (pintype "passive"))
      (node (ref "U6") (pin "B4") (pinfunction "IF1_B4") (pintype "passive"))
      (node (ref "U6") (pin "C4") (pinfunction "IF0_C4") (pintype "passive"))
    )
    (net (code "123") (name "VDD_1V8_CAM") (class "Default")
      (node (ref "U13") (pin "3") (pinfunction "2E_3") (pintype "passive"))
      (node (ref "U13") (pin "7") (pinfunction "1E_7") (pintype "passive"))
    )
    (net (code "124") (name "VSYS") (class "Default") (node (ref "R40") (pin "2") (pintype "passive")))
    (net (code "125") (name "unconnected-(U5H-GPIO_AD_04-PadM13)") (class "Default")
      (node (ref "U5") (pin "M13") (pinfunction "GPIO_AD_04_M13") (pintype "bidirectional+no_connect"))
    )
    (net (code "126") (name "unconnected-(U6-NC-PadB1)") (class "Default")
      (node (ref "U6") (pin "B1") (pinfunction "NC_B1") (pintype "passive+no_connect"))
    )
    (net (code "127") (name "unconnected-(U6-NC-PadC1)") (class "Default")
      (node (ref "U6") (pin "C1") (pinfunction "NC_C1") (pintype "passive+no_connect"))
    )
  )
)
